# mainboard_interface_v1_4.net
KiCad netlist of a schematic drawn in Altium Designer
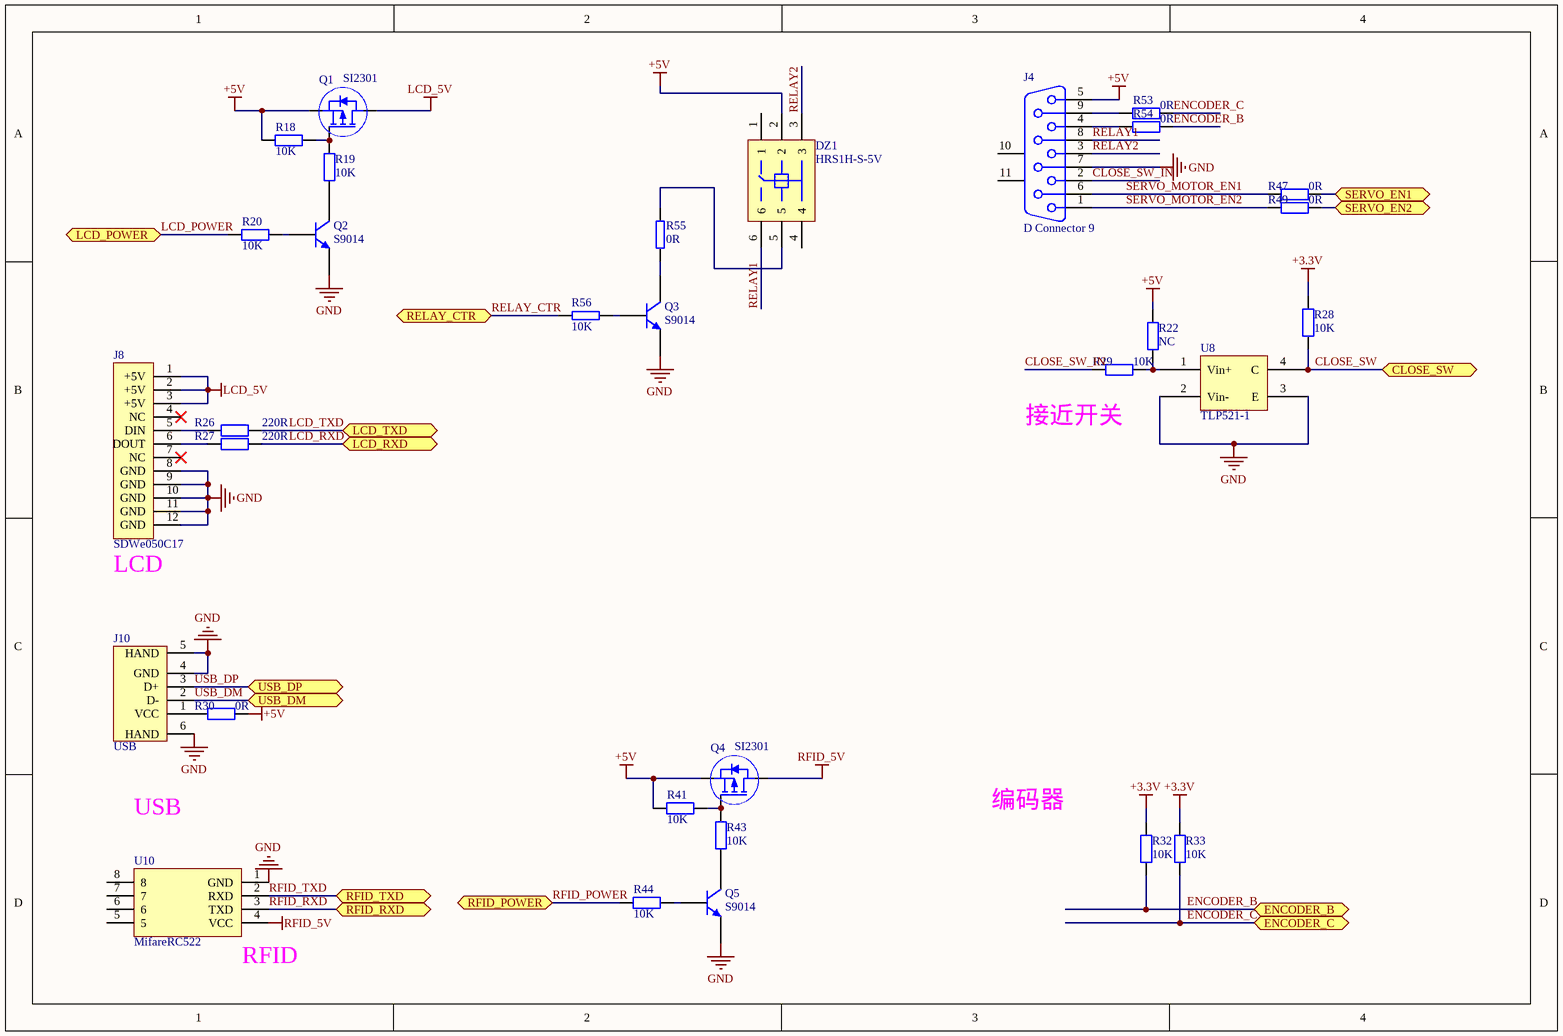
[diagram p0: mainboard_interface.v1.4.SchDoc]

(export (version "E")
  (design (tool "Eeschema 10.0.6"))
  (components
    (comp (ref "DZ1")
      (value "HRS1H-S-5V")
      (footprint "HRS1H-S-DC5")
      (libsource (lib "Componet") (part "HRS1H-S-5V"))
    )
    (comp (ref "J4")
      (value "D Connector 9")
      (footprint "DSUB1.385-2H9")
      (description "Receptacle Assembly, 9 Position, Right Angle")
      (fields (field (name "PUBLISHER") "Altium Limited"))
      (libsource (lib "Miscellaneous Connectors") (part "D Connector 9"))
    )
    (comp (ref "J8")
      (value "SDWe050C17")
      (footprint "FCC1.0-10")
      (libsource (lib "Connector") (part "SH-12"))
    )
    (comp (ref "J10") (value "USB") (footprint "USB_FEMALE_A") (libsource (lib "Connector") (part "USB")))
    (comp (ref "Q1") (value "SI2301") (footprint "MOS-N_SOT-23") (libsource (lib "*") (part "MOS-P_SOT-23")))
    (comp (ref "Q2") (value "S9014") (footprint "901X_SOT-23") (libsource (lib "Componet") (part "NPN")))
    (comp (ref "Q3") (value "S9014") (footprint "901X_SOT-23") (libsource (lib "Componet") (part "NPN")))
    (comp (ref "Q4") (value "SI2301") (footprint "MOS-N_SOT-23") (libsource (lib "*") (part "MOS-P_SOT-23")))
    (comp (ref "Q5") (value "S9014") (footprint "901X_SOT-23") (libsource (lib "Componet") (part "NPN")))
    (comp (ref "R18")
      (value "10K")
      (footprint "0805")
      (description "Resistor")
      (fields (field (name "PUBLISHER") "Altium Limited"))
      (libsource (lib "") (part "Res2_1"))
    )
    (comp (ref "R19")
      (value "10K")
      (footprint "0805")
      (description "Resistor")
      (fields (field (name "PUBLISHER") "Altium Limited"))
      (libsource (lib "") (part "Res2_3"))
    )
    (comp (ref "R20")
      (value "10K")
      (footprint "0805")
      (description "Resistor")
      (fields (field (name "PUBLISHER") "Altium Limited"))
      (libsource (lib "") (part "Res2_1"))
    )
    (comp (ref "R22")
      (value "NC")
      (footprint "0805")
      (description "Resistor")
      (fields (field (name "PUBLISHER") "Altium Limited"))
      (libsource (lib "") (part "Res2_2"))
    )
    (comp (ref "R26")
      (value "220R")
      (footprint "0805")
      (description "Resistor")
      (fields (field (name "PUBLISHER") "Altium Limited"))
      (libsource (lib "") (part "Res2_1"))
    )
    (comp (ref "R27")
      (value "220R")
      (footprint "0805")
      (description "Resistor")
      (fields (field (name "PUBLISHER") "Altium Limited"))
      (libsource (lib "") (part "Res2_1"))
    )
    (comp (ref "R28")
      (value "10K")
      (footprint "0805")
      (description "Resistor")
      (fields (field (name "PUBLISHER") "Altium Limited"))
      (libsource (lib "") (part "Res2_2"))
    )
    (comp (ref "R29")
      (value "10K")
      (footprint "0805")
      (description "Resistor")
      (fields (field (name "PUBLISHER") "Altium Limited"))
      (libsource (lib "TIAN's Schlib") (part "Res2"))
    )
    (comp (ref "R30")
      (value "0R")
      (footprint "0805")
      (description "Resistor")
      (fields (field (name "PUBLISHER") "Altium Limited"))
      (libsource (lib "TIAN's Schlib") (part "Res2"))
    )
    (comp (ref "R32")
      (value "10K")
      (footprint "0805")
      (description "Resistor")
      (fields (field (name "PUBLISHER") "Altium Limited"))
      (libsource (lib "") (part "Res2_2"))
    )
    (comp (ref "R33")
      (value "10K")
      (footprint "0805")
      (description "Resistor")
      (fields (field (name "PUBLISHER") "Altium Limited"))
      (libsource (lib "") (part "Res2_2"))
    )
    (comp (ref "R41")
      (value "10K")
      (footprint "0805")
      (description "Resistor")
      (fields (field (name "PUBLISHER") "Altium Limited"))
      (libsource (lib "") (part "Res2_1"))
    )
    (comp (ref "R43")
      (value "10K")
      (footprint "0805")
      (description "Resistor")
      (fields (field (name "PUBLISHER") "Altium Limited"))
      (libsource (lib "") (part "Res2_3"))
    )
    (comp (ref "R44")
      (value "10K")
      (footprint "0805")
      (description "Resistor")
      (fields (field (name "PUBLISHER") "Altium Limited"))
      (libsource (lib "") (part "Res2_1"))
    )
    (comp (ref "R47")
      (value "0R")
      (footprint "0805")
      (description "Resistor")
      (fields (field (name "PUBLISHER") "Altium Limited"))
      (libsource (lib "TIAN's Schlib") (part "Res2"))
    )
    (comp (ref "R49")
      (value "0R")
      (footprint "0805")
      (description "Resistor")
      (fields (field (name "PUBLISHER") "Altium Limited"))
      (libsource (lib "TIAN's Schlib") (part "Res2"))
    )
    (comp (ref "R53")
      (value "0R")
      (footprint "0805")
      (description "Resistor")
      (fields (field (name "PUBLISHER") "Altium Limited"))
      (libsource (lib "") (part "Res2_1"))
    )
    (comp (ref "R54")
      (value "0R")
      (footprint "0805")
      (description "Resistor")
      (fields (field (name "PUBLISHER") "Altium Limited"))
      (libsource (lib "") (part "Res2_1"))
    )
    (comp (ref "R55")
      (value "0R")
      (footprint "0805")
      (description "电阻")
      (libsource (lib "Component") (part "RES"))
    )
    (comp (ref "R56")
      (value "10K")
      (footprint "0805")
      (description "电阻")
      (libsource (lib "Component") (part "RES"))
    )
    (comp (ref "U8") (value "TLP521-1") (footprint "TLP521-1") (libsource (lib "Chip") (part "TLP521-1")))
    (comp (ref "U10")
      (value "MifareRC522")
      (footprint "MifareRC522")
      (libsource (lib "Componet") (part "MifareRC522"))
    )
  )
  (nets
    (net (code "1") (name "+3.3V") (class "Default")
      (node (ref "R28") (pin "1") (pinfunction "1_1") (pintype "passive"))
      (node (ref "R32") (pin "1") (pinfunction "1_1") (pintype "passive"))
      (node (ref "R33") (pin "1") (pinfunction "1_1") (pintype "passive"))
    )
    (net (code "2") (name "+5V") (class "Default")
      (node (ref "DZ1") (pin "2") (pinfunction "2_2") (pintype "passive"))
      (node (ref "J4") (pin "5") (pinfunction "5_5") (pintype "passive"))
      (node (ref "Q1") (pin "S") (pinfunction "S_S") (pintype "passive"))
      (node (ref "Q4") (pin "S") (pinfunction "S_S") (pintype "passive"))
      (node (ref "R18") (pin "1") (pinfunction "1_1") (pintype "passive"))
      (node (ref "R22") (pin "1") (pinfunction "1_1") (pintype "passive"))
      (node (ref "R30") (pin "1") (pinfunction "1_1") (pintype "passive"))
      (node (ref "R41") (pin "1") (pinfunction "1_1") (pintype "passive"))
    )
    (net (code "3") (name "/CLOSE_SW") (class "Default")
      (node (ref "R28") (pin "2") (pinfunction "2_2") (pintype "passive"))
      (node (ref "U8") (pin "4") (pinfunction "C_4") (pintype "passive"))
    )
    (net (code "4") (name "/CLOSE_SW_IN") (class "Default")
      (node (ref "J4") (pin "2") (pinfunction "2_2") (pintype "passive"))
      (node (ref "R29") (pin "2") (pinfunction "2_2") (pintype "passive"))
    )
    (net (code "5") (name "/ENCODER_B") (class "Default")
      (node (ref "R32") (pin "2") (pinfunction "2_2") (pintype "passive"))
      (node (ref "R54") (pin "2") (pinfunction "2_2") (pintype "passive"))
    )
    (net (code "6") (name "/ENCODER_C") (class "Default")
      (node (ref "R33") (pin "2") (pinfunction "2_2") (pintype "passive"))
      (node (ref "R53") (pin "2") (pinfunction "2_2") (pintype "passive"))
    )
    (net (code "7") (name "/LCD_POWER") (class "Default")
      (node (ref "R20") (pin "1") (pinfunction "1_1") (pintype "passive"))
    )
    (net (code "8") (name "/LCD_RXD") (class "Default")
      (node (ref "R27") (pin "2") (pinfunction "2_2") (pintype "passive"))
    )
    (net (code "9") (name "/LCD_TXD") (class "Default")
      (node (ref "R26") (pin "2") (pinfunction "2_2") (pintype "passive"))
    )
    (net (code "10") (name "/RELAY1") (class "Default")
      (node (ref "DZ1") (pin "6") (pinfunction "6_6") (pintype "passive"))
      (node (ref "J4") (pin "8") (pinfunction "8_8") (pintype "passive"))
    )
    (net (code "11") (name "/RELAY2") (class "Default")
      (node (ref "DZ1") (pin "3") (pinfunction "3_3") (pintype "passive"))
      (node (ref "J4") (pin "3") (pinfunction "3_3") (pintype "passive"))
    )
    (net (code "12") (name "/RELAY_CTR") (class "Default")
      (node (ref "R56") (pin "2") (pinfunction "2_2") (pintype "passive"))
    )
    (net (code "13") (name "/RFID_POWER") (class "Default")
      (node (ref "R44") (pin "1") (pinfunction "1_1") (pintype "passive"))
    )
    (net (code "14") (name "/RFID_RXD") (class "Default")
      (node (ref "U10") (pin "3") (pinfunction "TXD_3") (pintype "passive"))
    )
    (net (code "15") (name "/RFID_TXD") (class "Default")
      (node (ref "U10") (pin "2") (pinfunction "RXD_2") (pintype "passive"))
    )
    (net (code "16") (name "/SERVO_EN1") (class "Default")
      (node (ref "R47") (pin "1") (pinfunction "1_1") (pintype "passive"))
    )
    (net (code "17") (name "/SERVO_EN2") (class "Default")
      (node (ref "R49") (pin "1") (pinfunction "1_1") (pintype "passive"))
    )
    (net (code "18") (name "/SERVO_MOTOR_EN1") (class "Default")
      (node (ref "J4") (pin "6") (pinfunction "6_6") (pintype "passive"))
      (node (ref "R47") (pin "2") (pinfunction "2_2") (pintype "passive"))
    )
    (net (code "19") (name "/SERVO_MOTOR_EN2") (class "Default")
      (node (ref "J4") (pin "1") (pinfunction "1_1") (pintype "passive"))
      (node (ref "R49") (pin "2") (pinfunction "2_2") (pintype "passive"))
    )
    (net (code "20") (name "/USB_DM") (class "Default")
      (node (ref "J10") (pin "2") (pinfunction "D-_2") (pintype "passive"))
    )
    (net (code "21") (name "/USB_DP") (class "Default")
      (node (ref "J10") (pin "3") (pinfunction "D+_3") (pintype "passive"))
    )
    (net (code "22") (name "GND") (class "Default")
      (node (ref "J10") (pin "4") (pinfunction "GND_4") (pintype "passive"))
      (node (ref "J10") (pin "5") (pinfunction "HAND_5") (pintype "passive"))
      (node (ref "J10") (pin "6") (pinfunction "HAND_6") (pintype "passive"))
      (node (ref "J4") (pin "7") (pinfunction "7_7") (pintype "passive"))
      (node (ref "J8") (pin "10") (pinfunction "GND_10") (pintype "passive"))
      (node (ref "J8") (pin "11") (pinfunction "GND_11") (pintype "passive"))
      (node (ref "J8") (pin "12") (pinfunction "GND_12") (pintype "passive"))
      (node (ref "J8") (pin "8") (pinfunction "GND_8") (pintype "passive"))
      (node (ref "J8") (pin "9") (pinfunction "GND_9") (pintype "passive"))
      (node (ref "Q2") (pin "3") (pinfunction "E_3") (pintype "passive"))
      (node (ref "Q3") (pin "3") (pinfunction "E_3") (pintype "passive"))
      (node (ref "Q5") (pin "3") (pinfunction "E_3") (pintype "passive"))
      (node (ref "U10") (pin "1") (pinfunction "GND_1") (pintype "passive"))
      (node (ref "U8") (pin "2") (pinfunction "Vin-_2") (pintype "passive"))
      (node (ref "U8") (pin "3") (pinfunction "E_3") (pintype "passive"))
    )
    (net (code "23") (name "LCD_5V") (class "Default")
      (node (ref "J8") (pin "1") (pinfunction "+5V_1") (pintype "passive"))
      (node (ref "J8") (pin "2") (pinfunction "+5V_2") (pintype "passive"))
      (node (ref "J8") (pin "3") (pinfunction "+5V_3") (pintype "passive"))
      (node (ref "Q1") (pin "D") (pinfunction "D_D") (pintype "passive"))
    )
    (net (code "24") (name "Net-(DZ1-Pad5)") (class "Default")
      (node (ref "DZ1") (pin "5") (pinfunction "5_5") (pintype "passive"))
      (node (ref "R55") (pin "2") (pinfunction "2_2") (pintype "passive"))
    )
    (net (code "25") (name "Net-(J4-Pad4)") (class "Default")
      (node (ref "J4") (pin "4") (pinfunction "4_4") (pintype "passive"))
      (node (ref "R54") (pin "1") (pinfunction "1_1") (pintype "passive"))
    )
    (net (code "26") (name "Net-(J4-Pad9)") (class "Default")
      (node (ref "J4") (pin "9") (pinfunction "9_9") (pintype "passive"))
      (node (ref "R53") (pin "1") (pinfunction "1_1") (pintype "passive"))
    )
    (net (code "27") (name "Net-(J8-DIN)") (class "Default")
      (node (ref "J8") (pin "5") (pinfunction "DIN_5") (pintype "passive"))
      (node (ref "R26") (pin "1") (pinfunction "1_1") (pintype "passive"))
    )
    (net (code "28") (name "Net-(J8-DOUT)") (class "Default")
      (node (ref "J8") (pin "6") (pinfunction "DOUT_6") (pintype "passive"))
      (node (ref "R27") (pin "1") (pinfunction "1_1") (pintype "passive"))
    )
    (net (code "29") (name "Net-(J10-VCC)") (class "Default")
      (node (ref "J10") (pin "1") (pinfunction "VCC_1") (pintype "passive"))
      (node (ref "R30") (pin "2") (pinfunction "2_2") (pintype "passive"))
    )
    (net (code "30") (name "Net-(Q1-PadG)") (class "Default")
      (node (ref "Q1") (pin "G") (pinfunction "G_G") (pintype "passive"))
      (node (ref "R18") (pin "2") (pinfunction "2_2") (pintype "passive"))
      (node (ref "R19") (pin "2") (pinfunction "2_2") (pintype "passive"))
    )
    (net (code "31") (name "Net-(Q2-B)") (class "Default")
      (node (ref "Q2") (pin "2") (pinfunction "B_2") (pintype "passive"))
      (node (ref "R20") (pin "2") (pinfunction "2_2") (pintype "passive"))
    )
    (net (code "32") (name "Net-(Q2-C)") (class "Default")
      (node (ref "Q2") (pin "1") (pinfunction "C_1") (pintype "passive"))
      (node (ref "R19") (pin "1") (pinfunction "1_1") (pintype "passive"))
    )
    (net (code "33") (name "Net-(Q3-B)") (class "Default")
      (node (ref "Q3") (pin "2") (pinfunction "B_2") (pintype "passive"))
      (node (ref "R56") (pin "1") (pinfunction "1_1") (pintype "passive"))
    )
    (net (code "34") (name "Net-(Q3-C)") (class "Default")
      (node (ref "Q3") (pin "1") (pinfunction "C_1") (pintype "passive"))
      (node (ref "R55") (pin "1") (pinfunction "1_1") (pintype "passive"))
    )
    (net (code "35") (name "Net-(Q4-PadG)") (class "Default")
      (node (ref "Q4") (pin "G") (pinfunction "G_G") (pintype "passive"))
      (node (ref "R41") (pin "2") (pinfunction "2_2") (pintype "passive"))
      (node (ref "R43") (pin "2") (pinfunction "2_2") (pintype "passive"))
    )
    (net (code "36") (name "Net-(Q5-B)") (class "Default")
      (node (ref "Q5") (pin "2") (pinfunction "B_2") (pintype "passive"))
      (node (ref "R44") (pin "2") (pinfunction "2_2") (pintype "passive"))
    )
    (net (code "37") (name "Net-(Q5-C)") (class "Default")
      (node (ref "Q5") (pin "1") (pinfunction "C_1") (pintype "passive"))
      (node (ref "R43") (pin "1") (pinfunction "1_1") (pintype "passive"))
    )
    (net (code "38") (name "Net-(U8-Vin+)") (class "Default")
      (node (ref "R22") (pin "2") (pinfunction "2_2") (pintype "passive"))
      (node (ref "R29") (pin "1") (pinfunction "1_1") (pintype "passive"))
      (node (ref "U8") (pin "1") (pinfunction "Vin+_1") (pintype "passive"))
    )
    (net (code "39") (name "RFID_5V") (class "Default")
      (node (ref "Q4") (pin "D") (pinfunction "D_D") (pintype "passive"))
      (node (ref "U10") (pin "4") (pinfunction "VCC_4") (pintype "passive"))
    )
    (net (code "40") (name "unconnected-(DZ1-Pad1)") (class "Default")
      (node (ref "DZ1") (pin "1") (pinfunction "1_1") (pintype "passive"))
    )
    (net (code "41") (name "unconnected-(DZ1-Pad4)") (class "Default")
      (node (ref "DZ1") (pin "4") (pinfunction "4_4") (pintype "passive"))
    )
    (net (code "42") (name "unconnected-(J4-MH1-Pad10)") (class "Default")
      (node (ref "J4") (pin "10") (pinfunction "MH1_10") (pintype "passive"))
    )
    (net (code "43") (name "unconnected-(J4-MH2-Pad11)") (class "Default")
      (node (ref "J4") (pin "11") (pinfunction "MH2_11") (pintype "passive"))
    )
    (net (code "44") (name "unconnected-(J8-NC-Pad4)") (class "Default")
      (node (ref "J8") (pin "4") (pinfunction "NC_4") (pintype "passive+no_connect"))
    )
    (net (code "45") (name "unconnected-(J8-NC-Pad7)") (class "Default")
      (node (ref "J8") (pin "7") (pinfunction "NC_7") (pintype "passive+no_connect"))
    )
    (net (code "46") (name "unconnected-(U10-Pad5)") (class "Default")
      (node (ref "U10") (pin "5") (pinfunction "5_5") (pintype "passive"))
    )
    (net (code "47") (name "unconnected-(U10-Pad6)") (class "Default")
      (node (ref "U10") (pin "6") (pinfunction "6_6") (pintype "passive"))
    )
    (net (code "48") (name "unconnected-(U10-Pad7)") (class "Default")
      (node (ref "U10") (pin "7") (pinfunction "7_7") (pintype "passive"))
    )
    (net (code "49") (name "unconnected-(U10-Pad8)") (class "Default")
      (node (ref "U10") (pin "8") (pinfunction "8_8") (pintype "passive"))
    )
  )
)
